# UniConnector.net
KiCad netlist of a schematic drawn in Altium Designer
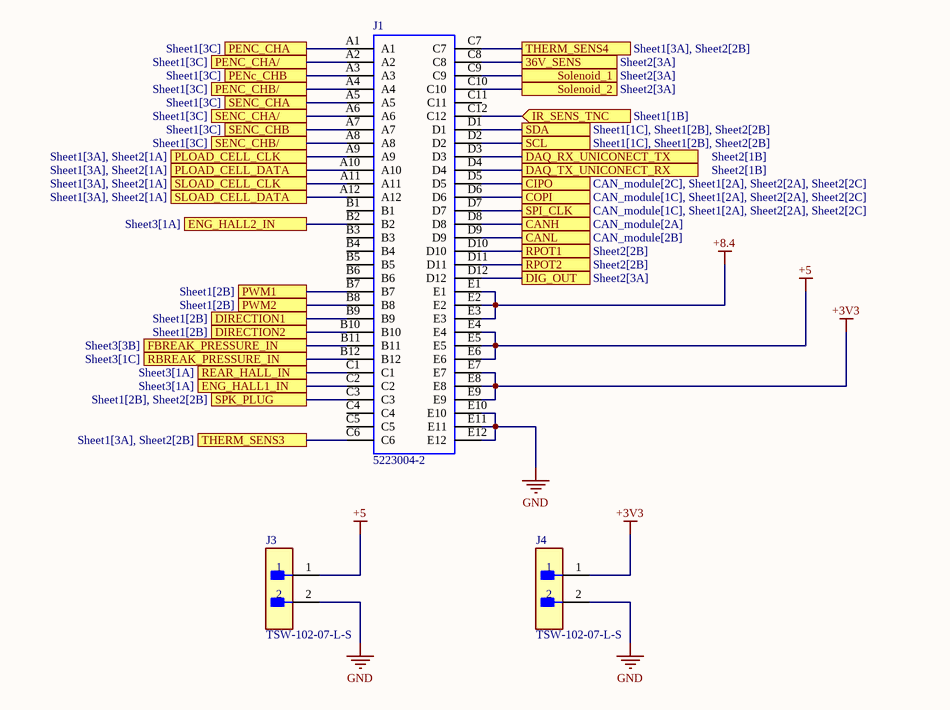
[diagram p0: UniConnector.SchDoc]

(export (version "E")
  (design (tool "Eeschema 10.0.6"))
  (components
    (comp (ref "J1")
      (value "5223004-2")
      (footprint "52230042")
      (description "Conn Backplane RCP 60 POS 2mm Solder RA Thru-Hole Tube")
      (fields (field (name "MOUSER PART NUMBER") "571-5223004-2"))
      (libsource (lib "5223004-2") (part "5223004-2"))
    )
    (comp (ref "J3")
      (value "TSW-102-07-L-S")
      (footprint "FP-TSW-102-07-L-S-MFG")
      (description "CONN HEADER VERT 2POS 2.54MM")
      (libsource (lib "Altium Content Vault") (part "3bc925449376181038e59eaffc5286c"))
    )
    (comp (ref "J4")
      (value "TSW-102-07-L-S")
      (footprint "FP-TSW-102-07-L-S-MFG")
      (description "CONN HEADER VERT 2POS 2.54MM")
      (libsource (lib "Altium Content Vault") (part "3bc925449376181038e59eaffc5286c"))
    )
  )
  (nets
    (net (code "1") (name "+3V3") (class "Default")
      (node (ref "J1") (pin "E7") (pinfunction "E7_E7") (pintype "passive"))
      (node (ref "J1") (pin "E8") (pinfunction "E8_E8") (pintype "passive"))
      (node (ref "J1") (pin "E9") (pinfunction "E9_E9") (pintype "passive"))
      (node (ref "J4") (pin "1") (pinfunction "1_1") (pintype "passive"))
    )
    (net (code "2") (name "+5") (class "Default")
      (node (ref "J1") (pin "E4") (pinfunction "E4_E4") (pintype "passive"))
      (node (ref "J1") (pin "E5") (pinfunction "E5_E5") (pintype "passive"))
      (node (ref "J1") (pin "E6") (pinfunction "E6_E6") (pintype "passive"))
      (node (ref "J3") (pin "1") (pinfunction "1_1") (pintype "passive"))
    )
    (net (code "3") (name "+8.4") (class "Default")
      (node (ref "J1") (pin "E1") (pinfunction "E1_E1") (pintype "passive"))
      (node (ref "J1") (pin "E2") (pinfunction "E2_E2") (pintype "passive"))
      (node (ref "J1") (pin "E3") (pinfunction "E3_E3") (pintype "passive"))
    )
    (net (code "4") (name "/36V_SENS") (class "Default")
      (node (ref "J1") (pin "C8") (pinfunction "C8_C8") (pintype "passive"))
    )
    (net (code "5") (name "/CANH") (class "Default")
      (node (ref "J1") (pin "D8") (pinfunction "D8_D8") (pintype "passive"))
    )
    (net (code "6") (name "/CANL") (class "Default")
      (node (ref "J1") (pin "D9") (pinfunction "D9_D9") (pintype "passive"))
    )
    (net (code "7") (name "/CIPO") (class "Default")
      (node (ref "J1") (pin "D5") (pinfunction "D5_D5") (pintype "passive"))
    )
    (net (code "8") (name "/COPI") (class "Default")
      (node (ref "J1") (pin "D6") (pinfunction "D6_D6") (pintype "passive"))
    )
    (net (code "9") (name "/DAQ_RX_UNICONECT_TX") (class "Default")
      (node (ref "J1") (pin "D3") (pinfunction "D3_D3") (pintype "passive"))
    )
    (net (code "10") (name "/DAQ_TX_UNICONECT_RX") (class "Default")
      (node (ref "J1") (pin "D4") (pinfunction "D4_D4") (pintype "passive"))
    )
    (net (code "11") (name "/DIG_OUT") (class "Default")
      (node (ref "J1") (pin "D12") (pinfunction "D12_D12") (pintype "passive"))
    )
    (net (code "12") (name "/DIRECTION1") (class "Default")
      (node (ref "J1") (pin "B9") (pinfunction "B9_B9") (pintype "passive"))
    )
    (net (code "13") (name "/DIRECTION2") (class "Default")
      (node (ref "J1") (pin "B10") (pinfunction "B10_B10") (pintype "passive"))
    )
    (net (code "14") (name "/ENG_HALL1_IN") (class "Default")
      (node (ref "J1") (pin "C2") (pinfunction "C2_C2") (pintype "passive"))
    )
    (net (code "15") (name "/ENG_HALL2_IN") (class "Default")
      (node (ref "J1") (pin "B2") (pinfunction "B2_B2") (pintype "passive"))
    )
    (net (code "16") (name "/FBREAK_PRESSURE_IN") (class "Default")
      (node (ref "J1") (pin "B11") (pinfunction "B11_B11") (pintype "passive"))
    )
    (net (code "17") (name "/IR_SENS_TNC") (class "Default")
      (node (ref "J1") (pin "C12") (pinfunction "C12_C12") (pintype "passive"))
    )
    (net (code "18") (name "/PENC_CHA") (class "Default")
      (node (ref "J1") (pin "A1") (pinfunction "A1_A1") (pintype "passive"))
    )
    (net (code "19") (name "/PENC_CHA{slash}") (class "Default")
      (node (ref "J1") (pin "A2") (pinfunction "A2_A2") (pintype "passive"))
    )
    (net (code "20") (name "/PENC_CHB{slash}") (class "Default")
      (node (ref "J1") (pin "A4") (pinfunction "A4_A4") (pintype "passive"))
    )
    (net (code "21") (name "/PENc_CHB") (class "Default")
      (node (ref "J1") (pin "A3") (pinfunction "A3_A3") (pintype "passive"))
    )
    (net (code "22") (name "/PLOAD_CELL_CLK") (class "Default")
      (node (ref "J1") (pin "A9") (pinfunction "A9_A9") (pintype "passive"))
    )
    (net (code "23") (name "/PLOAD_CELL_DATA") (class "Default")
      (node (ref "J1") (pin "A10") (pinfunction "A10_A10") (pintype "passive"))
    )
    (net (code "24") (name "/PWM1") (class "Default")
      (node (ref "J1") (pin "B7") (pinfunction "B7_B7") (pintype "passive"))
    )
    (net (code "25") (name "/PWM2") (class "Default")
      (node (ref "J1") (pin "B8") (pinfunction "B8_B8") (pintype "passive"))
    )
    (net (code "26") (name "/RBREAK_PRESSURE_IN") (class "Default")
      (node (ref "J1") (pin "B12") (pinfunction "B12_B12") (pintype "passive"))
    )
    (net (code "27") (name "/REAR_HALL_IN") (class "Default")
      (node (ref "J1") (pin "C1") (pinfunction "C1_C1") (pintype "passive"))
    )
    (net (code "28") (name "/RPOT1") (class "Default")
      (node (ref "J1") (pin "D10") (pinfunction "D10_D10") (pintype "passive"))
    )
    (net (code "29") (name "/RPOT2") (class "Default")
      (node (ref "J1") (pin "D11") (pinfunction "D11_D11") (pintype "passive"))
    )
    (net (code "30") (name "/SCL") (class "Default")
      (node (ref "J1") (pin "D2") (pinfunction "D2_D2") (pintype "passive"))
    )
    (net (code "31") (name "/SDA") (class "Default")
      (node (ref "J1") (pin "D1") (pinfunction "D1_D1") (pintype "passive"))
    )
    (net (code "32") (name "/SENC_CHA") (class "Default")
      (node (ref "J1") (pin "A5") (pinfunction "A5_A5") (pintype "passive"))
    )
    (net (code "33") (name "/SENC_CHA{slash}") (class "Default")
      (node (ref "J1") (pin "A6") (pinfunction "A6_A6") (pintype "passive"))
    )
    (net (code "34") (name "/SENC_CHB") (class "Default")
      (node (ref "J1") (pin "A7") (pinfunction "A7_A7") (pintype "passive"))
    )
    (net (code "35") (name "/SENC_CHB{slash}") (class "Default")
      (node (ref "J1") (pin "A8") (pinfunction "A8_A8") (pintype "passive"))
    )
    (net (code "36") (name "/SLOAD_CELL_CLK") (class "Default")
      (node (ref "J1") (pin "A11") (pinfunction "A11_A11") (pintype "passive"))
    )
    (net (code "37") (name "/SLOAD_CELL_DATA") (class "Default")
      (node (ref "J1") (pin "A12") (pinfunction "A12_A12") (pintype "passive"))
    )
    (net (code "38") (name "/SPI_CLK") (class "Default")
      (node (ref "J1") (pin "D7") (pinfunction "D7_D7") (pintype "passive"))
    )
    (net (code "39") (name "/SPK_PLUG") (class "Default")
      (node (ref "J1") (pin "C3") (pinfunction "C3_C3") (pintype "passive"))
    )
    (net (code "40") (name "/Solenoid_1") (class "Default")
      (node (ref "J1") (pin "C9") (pinfunction "C9_C9") (pintype "passive"))
    )
    (net (code "41") (name "/Solenoid_2") (class "Default")
      (node (ref "J1") (pin "C10") (pinfunction "C10_C10") (pintype "passive"))
    )
    (net (code "42") (name "/THERM_SENS3") (class "Default")
      (node (ref "J1") (pin "C6") (pinfunction "C6_C6") (pintype "passive"))
    )
    (net (code "43") (name "/THERM_SENS4") (class "Default")
      (node (ref "J1") (pin "C7") (pinfunction "C7_C7") (pintype "passive"))
    )
    (net (code "44") (name "GND") (class "Default")
      (node (ref "J1") (pin "E10") (pinfunction "E10_E10") (pintype "passive"))
      (node (ref "J1") (pin "E11") (pinfunction "E11_E11") (pintype "passive"))
      (node (ref "J1") (pin "E12") (pinfunction "E12_E12") (pintype "passive"))
      (node (ref "J3") (pin "2") (pinfunction "2_2") (pintype "passive"))
      (node (ref "J4") (pin "2") (pinfunction "2_2") (pintype "passive"))
    )
    (net (code "45") (name "unconnected-(J1-PadB1)") (class "Default")
      (node (ref "J1") (pin "B1") (pinfunction "B1_B1") (pintype "passive"))
    )
    (net (code "46") (name "unconnected-(J1-PadB3)") (class "Default")
      (node (ref "J1") (pin "B3") (pinfunction "B3_B3") (pintype "passive"))
    )
    (net (code "47") (name "unconnected-(J1-PadB4)") (class "Default")
      (node (ref "J1") (pin "B4") (pinfunction "B4_B4") (pintype "passive"))
    )
    (net (code "48") (name "unconnected-(J1-PadB5)") (class "Default")
      (node (ref "J1") (pin "B5") (pinfunction "B5_B5") (pintype "passive"))
    )
    (net (code "49") (name "unconnected-(J1-PadB6)") (class "Default")
      (node (ref "J1") (pin "B6") (pinfunction "B6_B6") (pintype "passive"))
    )
    (net (code "50") (name "unconnected-(J1-PadC4)") (class "Default")
      (node (ref "J1") (pin "C4") (pinfunction "C4_C4") (pintype "passive"))
    )
    (net (code "51") (name "unconnected-(J1-PadC5)") (class "Default")
      (node (ref "J1") (pin "C5") (pinfunction "C5_C5") (pintype "passive"))
    )
    (net (code "52") (name "unconnected-(J1-PadC11)") (class "Default")
      (node (ref "J1") (pin "C11") (pinfunction "C11_C11") (pintype "passive"))
    )
  )
)
